# 1_STM32F334R8T6Board_MCU.net
KiCad netlist of a schematic drawn in Altium Designer
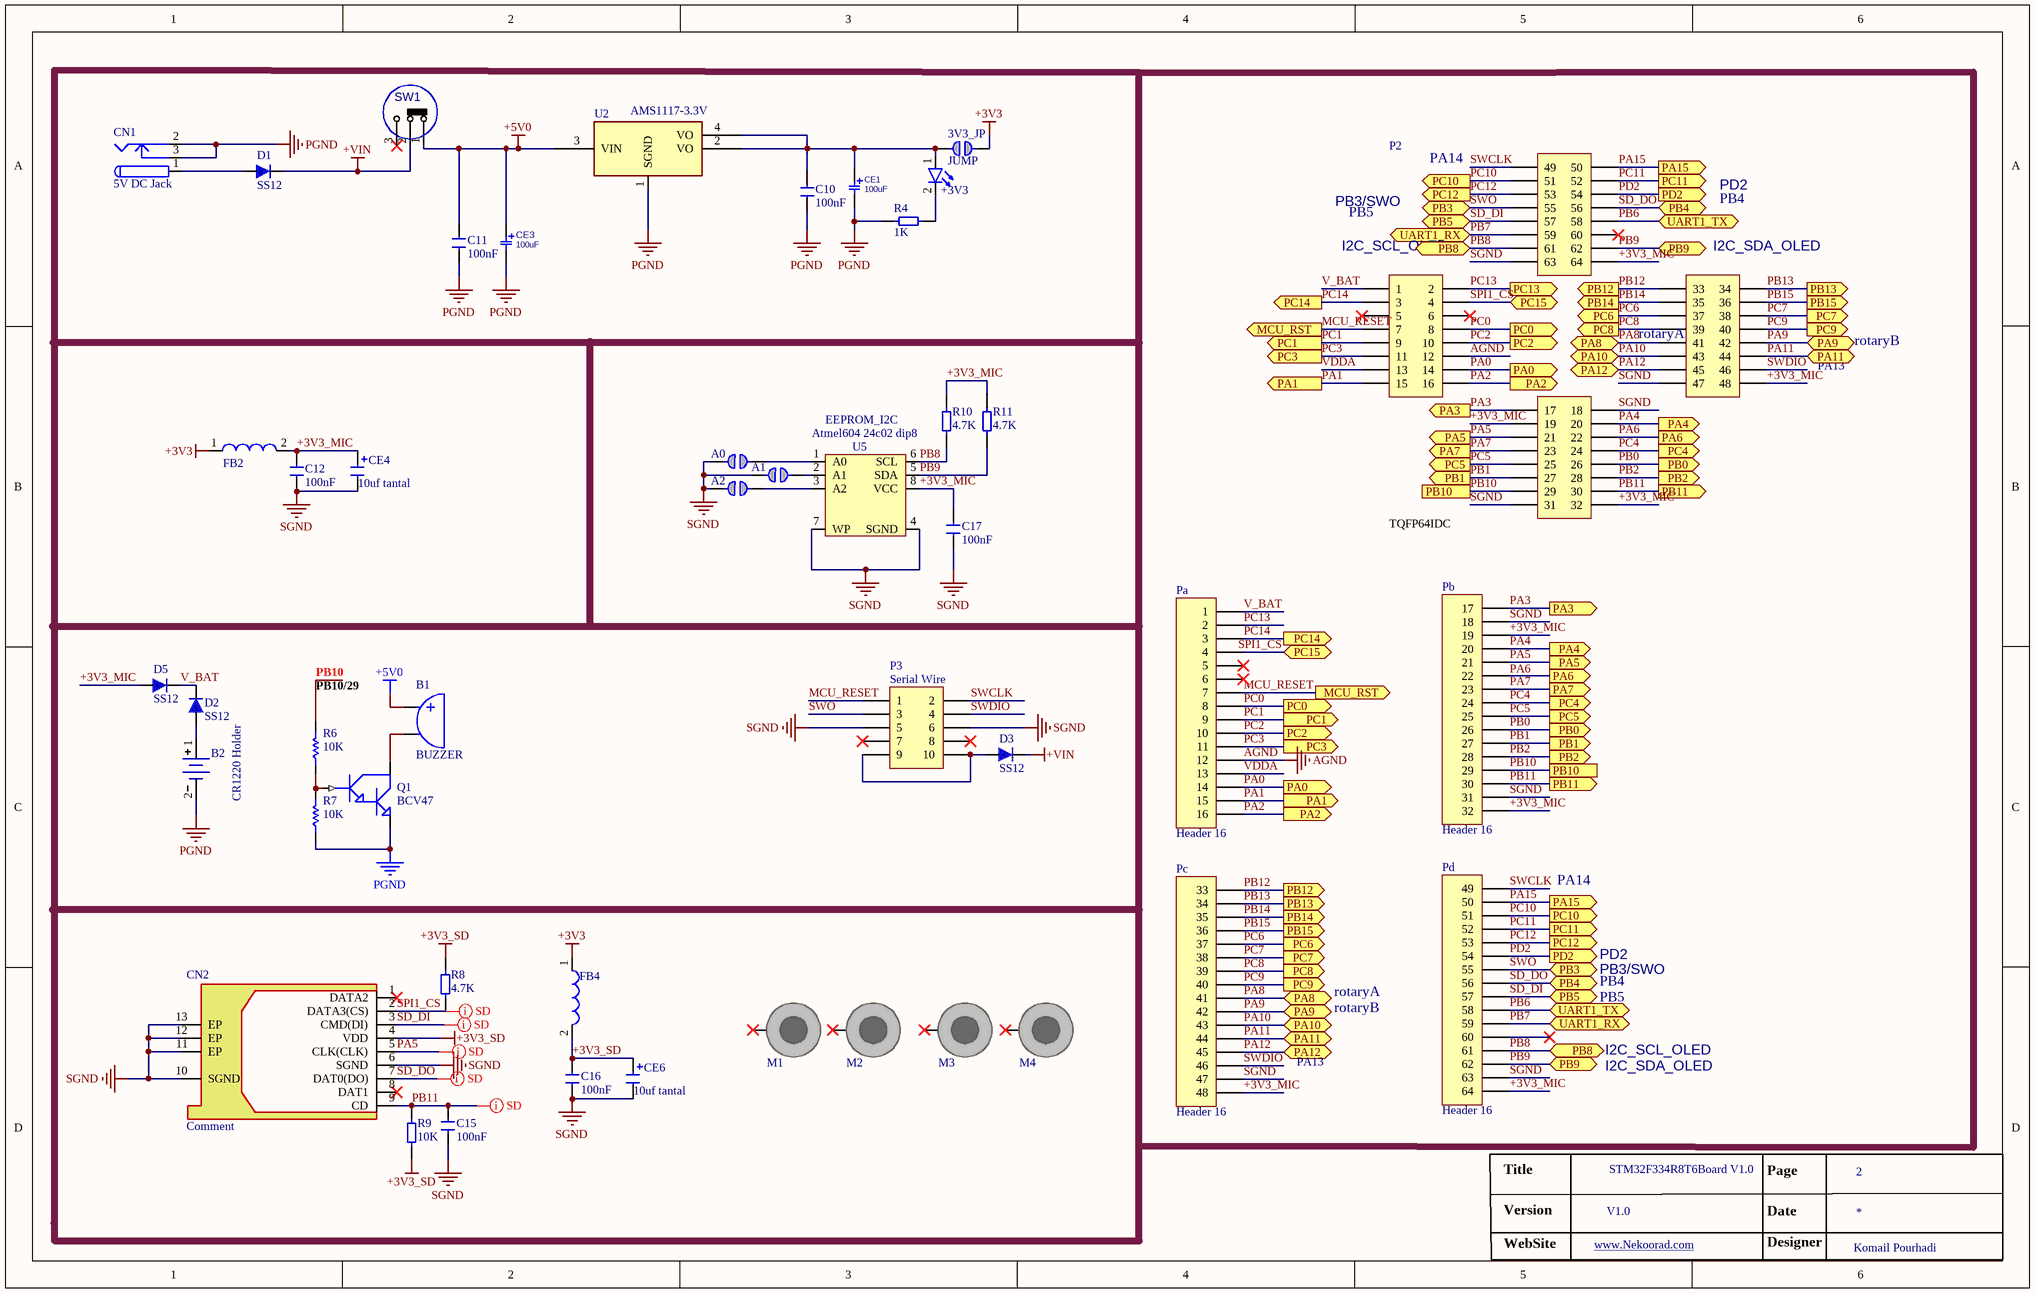
[diagram p0: [1]STM32F334R8T6Board_MCU.SchDoc]

(export (version "E")
  (design (tool "Eeschema 10.0.6"))
  (components
    (comp (ref "+3V3")
      (value "HB")
      (footprint "LED SMD 1206")
      (description "LED")
      (fields (field (name "DESIGNER") "Saeid Jorablo"))
      (libsource (lib "3D") (part "LED"))
    )
    (comp (ref "3V3_JP")
      (value "JUMP")
      (footprint "RES_1206")
      (libsource (lib "DotexGroup_LIB") (part "jumper SMD"))
    )
    (comp (ref "A0")
      (value "Comment")
      (footprint "HDR1X2")
      (libsource (lib "DotexGroup_LIB") (part "jumper SMD"))
    )
    (comp (ref "A1")
      (value "Comment")
      (footprint "HDR1X2")
      (libsource (lib "DotexGroup_LIB") (part "jumper SMD"))
    )
    (comp (ref "A2")
      (value "Comment")
      (footprint "HDR1X2")
      (libsource (lib "DotexGroup_LIB") (part "jumper SMD"))
    )
    (comp (ref "B1")
      (value "BUZZER")
      (footprint "BUZZ")
      (libsource (lib "Previous Backup of Device") (part "BUZZER"))
    )
    (comp (ref "B2")
      (value "CR1220 Holder")
      (footprint "Battery3")
      (libsource (lib "DotexGroup_LIB") (part "Battry Backup"))
    )
    (comp (ref "C10")
      (value "Comment")
      (footprint "SMD_CAP_1206")
      (fields (field (name "ALTIUM_UNNAMED_1") "100nF"))
      (libsource (lib "DotexGroup_LIB") (part "Capacitor SMD"))
    )
    (comp (ref "C11")
      (value "Comment")
      (footprint "SMD_CAP_1206")
      (fields (field (name "ALTIUM_UNNAMED_1") "100nF"))
      (libsource (lib "DotexGroup_LIB") (part "Capacitor SMD"))
    )
    (comp (ref "C12")
      (value "Comment")
      (footprint "SMD_CAP_1206")
      (fields (field (name "ALTIUM_UNNAMED_1") "100nF"))
      (libsource (lib "DotexGroup_LIB") (part "Capacitor SMD"))
    )
    (comp (ref "C15")
      (value "Comment")
      (footprint "SMD_CAP_1206")
      (fields (field (name "ALTIUM_UNNAMED_1") "100nF"))
      (libsource (lib "DotexGroup_LIB") (part "Capacitor SMD"))
    )
    (comp (ref "C16")
      (value "Comment")
      (footprint "SMD_CAP_1206")
      (fields (field (name "ALTIUM_UNNAMED_1") "100nF"))
      (libsource (lib "DotexGroup_LIB") (part "Capacitor SMD"))
    )
    (comp (ref "C17")
      (value "Comment")
      (footprint "SMD_CAP_1206")
      (fields (field (name "ALTIUM_UNNAMED_1") "100nF"))
      (libsource (lib "DotexGroup_LIB") (part "Capacitor SMD"))
    )
    (comp (ref "CE1")
      (value "100uF")
      (footprint "CAP-E-4")
      (description "CAP, THD, ELEC, 10uF, 25V")
      (fields (field (name "MANF") "MANF") (field (name "MANF_P#") "MANF_PART#"))
      (libsource (lib "DotexGroup_LIB") (part "CAP_THD_EL_10u25V"))
    )
    (comp (ref "CE3")
      (value "100uF")
      (footprint "CAP-E-4")
      (description "CAP, THD, ELEC, 10uF, 25V")
      (fields (field (name "MANF") "MANF") (field (name "MANF_P#") "MANF_PART#"))
      (libsource (lib "DotexGroup_LIB") (part "CAP_THD_EL_10u25V"))
    )
    (comp (ref "CE4")
      (value "10uf tantal")
      (footprint "cap-e-2")
      (libsource (lib "DotexGroup_LIB") (part "Capacitor Tantalium"))
    )
    (comp (ref "CE6")
      (value "10uf tantal")
      (footprint "cap-e-2")
      (libsource (lib "DotexGroup_LIB") (part "Capacitor Tantalium"))
    )
    (comp (ref "CN1")
      (value "5V DC Jack")
      (footprint "Power Jack")
      (libsource (lib "DotexGroup_LIB") (part "Power Jack"))
    )
    (comp (ref "CN2")
      (value "Comment")
      (footprint "Micro sd csrd")
      (libsource (lib "DotexGroup_LIB") (part "Micro SD Card"))
    )
    (comp (ref "D1")
      (value "SS12")
      (footprint "Diode SMA-M")
      (libsource (lib "DotexGroup_LIB") (part "1N4001"))
    )
    (comp (ref "D2")
      (value "SS12")
      (footprint "Diode SMA-M")
      (libsource (lib "DotexGroup_LIB") (part "1N4001"))
    )
    (comp (ref "D3")
      (value "SS12")
      (footprint "Diode SMA-M")
      (libsource (lib "DotexGroup_LIB") (part "1N4001"))
    )
    (comp (ref "D5")
      (value "SS12")
      (footprint "Diode SMA-M")
      (libsource (lib "DotexGroup_LIB") (part "1N4001"))
    )
    (comp (ref "FB2")
      (value "Comment")
      (footprint "r4p")
      (libsource (lib "DotexGroup_LIB") (part "Ferrit Bead"))
    )
    (comp (ref "FB4")
      (value "Comment")
      (footprint "r4p")
      (libsource (lib "DotexGroup_LIB") (part "Ferrit Bead"))
    )
    (comp (ref "M1")
      (value "Comment")
      (footprint "Stud-hole")
      (description "SCREW mouting, M1.6, 1.6mm diameter and 3.2mm PanHead")
      (libsource (lib "DotexGroup_LIB") (part "SCMH_M1P6"))
    )
    (comp (ref "M2")
      (value "Comment")
      (footprint "Stud-hole")
      (description "SCREW mouting, M1.6, 1.6mm diameter and 3.2mm PanHead")
      (libsource (lib "DotexGroup_LIB") (part "SCMH_M1P6"))
    )
    (comp (ref "M3")
      (value "Comment")
      (footprint "Stud-hole")
      (description "SCREW mouting, M1.6, 1.6mm diameter and 3.2mm PanHead")
      (libsource (lib "DotexGroup_LIB") (part "SCMH_M1P6"))
    )
    (comp (ref "M4")
      (value "Comment")
      (footprint "Stud-hole")
      (description "SCREW mouting, M1.6, 1.6mm diameter and 3.2mm PanHead")
      (libsource (lib "DotexGroup_LIB") (part "SCMH_M1P6"))
    )
    (comp (ref "P2")
      (value "TQFP64IDC")
      (footprint "tqfp64idc")
      (libsource (lib "Mylibrary2019") (part "TQFP64IDC"))
    )
    (comp (ref "P3")
      (value "Serial Wire")
      (footprint "IDC10-BOX")
      (description "Header, 5-Pin, Dual row")
      (fields (field (name "PUBLISHER") "Altium Limited"))
      (libsource (lib "Miscellaneous Connectors") (part "Header 5X2"))
    )
    (comp (ref "Pa")
      (value "Header 16")
      (footprint "HDR1X16")
      (description "Header, 16-Pin")
      (fields (field (name "PUBLISHER") "Altium Limited"))
      (libsource (lib "") (part "Header 16_1"))
    )
    (comp (ref "Pb")
      (value "Header 16")
      (footprint "HDR1X16")
      (description "Header, 16-Pin")
      (fields (field (name "PUBLISHER") "Altium Limited"))
      (libsource (lib "") (part "Header 16_3"))
    )
    (comp (ref "Pc")
      (value "Header 16")
      (footprint "HDR1X16")
      (description "Header, 16-Pin")
      (fields (field (name "PUBLISHER") "Altium Limited"))
      (libsource (lib "") (part "Header 16_2"))
    )
    (comp (ref "Pd")
      (value "Header 16")
      (footprint "HDR1X16")
      (description "Header, 16-Pin")
      (fields (field (name "PUBLISHER") "Altium Limited"))
      (libsource (lib "Miscellaneous Connectors") (part "Header 16"))
    )
    (comp (ref "Q1")
      (value "BCV47")
      (footprint "SOT23_BEC_M")
      (libsource (lib "MyAltiumLib") (part "NPN DAR"))
    )
    (comp (ref "R4")
      (value "Comment")
      (footprint "RES_1206")
      (fields (field (name "ALTIUM_UNNAMED_1") "1K"))
      (libsource (lib "DotexGroup_LIB") (part "Resistor SMD"))
    )
    (comp (ref "R6")
      (value "10K")
      (footprint "RES_1206")
      (description "Resistor")
      (fields (field (name "TOLERANCE") "5%") (field (name "POWER") "1/8 W"))
      (libsource (lib "My Library") (part "Resistor"))
    )
    (comp (ref "R7")
      (value "10K")
      (footprint "RES_1206")
      (description "Resistor")
      (fields (field (name "TOLERANCE") "5%") (field (name "POWER") "1/8 W"))
      (libsource (lib "My Library") (part "Resistor"))
    )
    (comp (ref "R8")
      (value "Comment")
      (footprint "RES_1206")
      (fields (field (name "ALTIUM_UNNAMED_1") "4.7K"))
      (libsource (lib "DotexGroup_LIB") (part "Resistor SMD"))
    )
    (comp (ref "R9")
      (value "Comment")
      (footprint "RES_1206")
      (fields (field (name "ALTIUM_UNNAMED_1") "10K"))
      (libsource (lib "DotexGroup_LIB") (part "Resistor SMD"))
    )
    (comp (ref "R10")
      (value "Comment")
      (footprint "RES_1206")
      (fields (field (name "ALTIUM_UNNAMED_1") "4.7K"))
      (libsource (lib "DotexGroup_LIB") (part "Resistor SMD"))
    )
    (comp (ref "R11")
      (value "Comment")
      (footprint "RES_1206")
      (fields (field (name "ALTIUM_UNNAMED_1") "4.7K"))
      (libsource (lib "DotexGroup_LIB") (part "Resistor SMD"))
    )
    (comp (ref "SW1")
      (value "SlideSwitch")
      (footprint "HDR1X3")
      (description "SWITCH, SLIDE, SPDT, 8.6X4.3mm, THD")
      (fields (field (name "MANF") "C&K") (field (name "MANF_PART#") "OS102011MS2QN1"))
      (libsource (lib "DotexGroup_LIB") (part "SWSLIDT_SPDT_S_8X4"))
    )
    (comp (ref "U2")
      (value "AMS1117-3.3V")
      (footprint "MP04A_M")
      (description "REG, Linear, LDO1V, 0.8A, SOT-223")
      (fields
        (field (name "MANF_P#") "LD1117, LM1117, AMS1117, TLV1117, REG1117, NCP1117, LT1117, SPX1117")
        (field (name "MANF") "TI, ON, ST")
      )
      (libsource (lib "DotexGroup_LIB") (part "VREG_1117_SOT223"))
    )
    (comp (ref "U5")
      (value "EEPROM_I2C")
      (footprint "dip8")
      (libsource (lib "DotexGroup_LIB") (part "AT24C128"))
    )
  )
  (nets
    (net (code "1") (name "+3V3") (class "Default")
      (node (ref "3V3_JP") (pin "2") (pintype "passive"))
      (node (ref "FB2") (pin "1") (pinfunction "1_1") (pintype "passive"))
      (node (ref "FB4") (pin "1") (pinfunction "1_1") (pintype "passive"))
    )
    (net (code "2") (name "+3V3_SD") (class "Default")
      (node (ref "C16") (pin "2") (pintype "passive"))
      (node (ref "CE6") (pin "1") (pintype "passive"))
      (node (ref "CN2") (pin "4") (pinfunction "VDD_4") (pintype "passive"))
      (node (ref "FB4") (pin "2") (pinfunction "2_2") (pintype "passive"))
      (node (ref "R8") (pin "1") (pintype "passive"))
      (node (ref "R9") (pin "2") (pintype "passive"))
    )
    (net (code "3") (name "+5V0") (class "Default")
      (node (ref "B1") (pin "1") (pintype "passive"))
      (node (ref "C11") (pin "2") (pintype "passive"))
      (node (ref "CE3") (pin "1") (pinfunction "1_1") (pintype "passive"))
      (node (ref "SW1") (pin "1") (pinfunction "P1_1") (pintype "passive"))
      (node (ref "U2") (pin "3") (pinfunction "VIN_3") (pintype "passive"))
    )
    (net (code "4") (name "+VIN") (class "Default")
      (node (ref "D1") (pin "2") (pinfunction "K_2") (pintype "passive"))
      (node (ref "D3") (pin "2") (pinfunction "K_2") (pintype "passive"))
      (node (ref "SW1") (pin "2") (pinfunction "P3_2") (pintype "passive"))
    )
    (net (code "5") (name "/+3V3_MIC") (class "Default")
      (node (ref "C12") (pin "2") (pintype "passive"))
      (node (ref "C17") (pin "2") (pintype "passive"))
      (node (ref "CE4") (pin "1") (pintype "passive"))
      (node (ref "D5") (pin "1") (pinfunction "A_1") (pintype "passive"))
      (node (ref "FB2") (pin "2") (pinfunction "2_2") (pintype "passive"))
      (node (ref "P2") (pin "19") (pinfunction "19_19") (pintype "passive"))
      (node (ref "P2") (pin "32") (pinfunction "32_32") (pintype "passive"))
      (node (ref "P2") (pin "48") (pinfunction "48_48") (pintype "passive"))
      (node (ref "P2") (pin "64") (pinfunction "64_64") (pintype "passive"))
      (node (ref "Pb") (pin "19") (pinfunction "19_19") (pintype "passive"))
      (node (ref "Pb") (pin "32") (pinfunction "32_32") (pintype "passive"))
      (node (ref "Pc") (pin "48") (pinfunction "48_48") (pintype "passive"))
      (node (ref "Pd") (pin "64") (pinfunction "64_64") (pintype "passive"))
      (node (ref "R10") (pin "1") (pintype "passive"))
      (node (ref "R11") (pin "1") (pintype "passive"))
      (node (ref "U5") (pin "8") (pinfunction "VCC_8") (pintype "passive"))
    )
    (net (code "6") (name "/MCU_RESET") (class "Default")
      (node (ref "P2") (pin "7") (pinfunction "7_7") (pintype "passive"))
      (node (ref "P3") (pin "1") (pinfunction "1_1") (pintype "passive"))
      (node (ref "Pa") (pin "7") (pinfunction "7_7") (pintype "passive"))
    )
    (net (code "7") (name "/PA0") (class "Default")
      (node (ref "P2") (pin "14") (pinfunction "14_14") (pintype "passive"))
      (node (ref "Pa") (pin "14") (pinfunction "14_14") (pintype "passive"))
    )
    (net (code "8") (name "/PA1") (class "Default")
      (node (ref "P2") (pin "15") (pinfunction "15_15") (pintype "passive"))
      (node (ref "Pa") (pin "15") (pinfunction "15_15") (pintype "passive"))
    )
    (net (code "9") (name "/PA2") (class "Default")
      (node (ref "P2") (pin "16") (pinfunction "16_16") (pintype "passive"))
      (node (ref "Pa") (pin "16") (pinfunction "16_16") (pintype "passive"))
    )
    (net (code "10") (name "/PA3") (class "Default")
      (node (ref "P2") (pin "17") (pinfunction "17_17") (pintype "passive"))
      (node (ref "Pb") (pin "17") (pinfunction "17_17") (pintype "passive"))
    )
    (net (code "11") (name "/PA4") (class "Default")
      (node (ref "P2") (pin "20") (pinfunction "20_20") (pintype "passive"))
      (node (ref "Pb") (pin "20") (pinfunction "20_20") (pintype "passive"))
    )
    (net (code "12") (name "/PA5") (class "Default")
      (node (ref "CN2") (pin "5") (pinfunction "CLK(CLK)_5") (pintype "passive"))
      (node (ref "P2") (pin "21") (pinfunction "21_21") (pintype "passive"))
      (node (ref "Pb") (pin "21") (pinfunction "21_21") (pintype "passive"))
    )
    (net (code "13") (name "/PA6") (class "Default")
      (node (ref "P2") (pin "22") (pinfunction "22_22") (pintype "passive"))
      (node (ref "Pb") (pin "22") (pinfunction "22_22") (pintype "passive"))
    )
    (net (code "14") (name "/PA7") (class "Default")
      (node (ref "P2") (pin "23") (pinfunction "23_23") (pintype "passive"))
      (node (ref "Pb") (pin "23") (pinfunction "23_23") (pintype "passive"))
    )
    (net (code "15") (name "/PA8") (class "Default")
      (node (ref "P2") (pin "41") (pinfunction "41_41") (pintype "passive"))
      (node (ref "Pc") (pin "41") (pinfunction "41_41") (pintype "passive"))
    )
    (net (code "16") (name "/PA9") (class "Default")
      (node (ref "P2") (pin "42") (pinfunction "42_42") (pintype "passive"))
      (node (ref "Pc") (pin "42") (pinfunction "42_42") (pintype "passive"))
    )
    (net (code "17") (name "/PA10") (class "Default")
      (node (ref "P2") (pin "43") (pinfunction "43_43") (pintype "passive"))
      (node (ref "Pc") (pin "43") (pinfunction "43_43") (pintype "passive"))
    )
    (net (code "18") (name "/PA11") (class "Default")
      (node (ref "P2") (pin "44") (pinfunction "44_44") (pintype "passive"))
      (node (ref "Pc") (pin "44") (pinfunction "44_44") (pintype "passive"))
    )
    (net (code "19") (name "/PA12") (class "Default")
      (node (ref "P2") (pin "45") (pinfunction "45_45") (pintype "passive"))
      (node (ref "Pc") (pin "45") (pinfunction "45_45") (pintype "passive"))
    )
    (net (code "20") (name "/PA15") (class "Default")
      (node (ref "P2") (pin "50") (pinfunction "50_50") (pintype "passive"))
      (node (ref "Pd") (pin "50") (pinfunction "50_50") (pintype "passive"))
    )
    (net (code "21") (name "/PB0") (class "Default")
      (node (ref "P2") (pin "26") (pinfunction "26_26") (pintype "passive"))
      (node (ref "Pb") (pin "26") (pinfunction "26_26") (pintype "passive"))
    )
    (net (code "22") (name "/PB1") (class "Default")
      (node (ref "P2") (pin "27") (pinfunction "27_27") (pintype "passive"))
      (node (ref "Pb") (pin "27") (pinfunction "27_27") (pintype "passive"))
    )
    (net (code "23") (name "/PB2") (class "Default")
      (node (ref "P2") (pin "28") (pinfunction "28_28") (pintype "passive"))
      (node (ref "Pb") (pin "28") (pinfunction "28_28") (pintype "passive"))
    )
    (net (code "24") (name "/PB6") (class "Default")
      (node (ref "P2") (pin "58") (pinfunction "58_58") (pintype "passive"))
      (node (ref "Pd") (pin "58") (pinfunction "58_58") (pintype "passive"))
    )
    (net (code "25") (name "/PB7") (class "Default")
      (node (ref "P2") (pin "59") (pinfunction "59_59") (pintype "passive"))
      (node (ref "Pd") (pin "59") (pinfunction "59_59") (pintype "passive"))
    )
    (net (code "26") (name "/PB8") (class "Default")
      (node (ref "P2") (pin "61") (pinfunction "61_61") (pintype "passive"))
      (node (ref "Pd") (pin "61") (pinfunction "61_61") (pintype "passive"))
      (node (ref "R10") (pin "2") (pintype "passive"))
      (node (ref "U5") (pin "6") (pinfunction "SCL_6") (pintype "passive"))
    )
    (net (code "27") (name "/PB9") (class "Default")
      (node (ref "P2") (pin "62") (pinfunction "62_62") (pintype "passive"))
      (node (ref "Pd") (pin "62") (pinfunction "62_62") (pintype "passive"))
      (node (ref "R11") (pin "2") (pintype "passive"))
      (node (ref "U5") (pin "5") (pinfunction "SDA_5") (pintype "passive"))
    )
    (net (code "28") (name "/PB10") (class "Default")
      (node (ref "P2") (pin "29") (pinfunction "29_29") (pintype "passive"))
      (node (ref "Pb") (pin "29") (pinfunction "29_29") (pintype "passive"))
      (node (ref "R6") (pin "2") (pinfunction "2_2") (pintype "passive"))
    )
    (net (code "29") (name "/PB11") (class "Default")
      (node (ref "C15") (pin "1") (pintype "passive"))
      (node (ref "CN2") (pin "9") (pinfunction "CD_9") (pintype "passive"))
      (node (ref "P2") (pin "30") (pinfunction "30_30") (pintype "passive"))
      (node (ref "Pb") (pin "30") (pinfunction "30_30") (pintype "passive"))
      (node (ref "R9") (pin "1") (pintype "passive"))
    )
    (net (code "30") (name "/PB12") (class "Default")
      (node (ref "P2") (pin "33") (pinfunction "33_33") (pintype "passive"))
      (node (ref "Pc") (pin "33") (pinfunction "33_33") (pintype "passive"))
    )
    (net (code "31") (name "/PB13") (class "Default")
      (node (ref "P2") (pin "34") (pinfunction "34_34") (pintype "passive"))
      (node (ref "Pc") (pin "34") (pinfunction "34_34") (pintype "passive"))
    )
    (net (code "32") (name "/PB14") (class "Default")
      (node (ref "P2") (pin "35") (pinfunction "35_35") (pintype "passive"))
      (node (ref "Pc") (pin "35") (pinfunction "35_35") (pintype "passive"))
    )
    (net (code "33") (name "/PB15") (class "Default")
      (node (ref "P2") (pin "36") (pinfunction "36_36") (pintype "passive"))
      (node (ref "Pc") (pin "36") (pinfunction "36_36") (pintype "passive"))
    )
    (net (code "34") (name "/PC0") (class "Default")
      (node (ref "P2") (pin "8") (pinfunction "8_8") (pintype "passive"))
      (node (ref "Pa") (pin "8") (pinfunction "8_8") (pintype "passive"))
    )
    (net (code "35") (name "/PC1") (class "Default")
      (node (ref "P2") (pin "9") (pinfunction "9_9") (pintype "passive"))
      (node (ref "Pa") (pin "9") (pinfunction "9_9") (pintype "passive"))
    )
    (net (code "36") (name "/PC2") (class "Default")
      (node (ref "P2") (pin "10") (pinfunction "10_10") (pintype "passive"))
      (node (ref "Pa") (pin "10") (pinfunction "10_10") (pintype "passive"))
    )
    (net (code "37") (name "/PC3") (class "Default")
      (node (ref "P2") (pin "11") (pinfunction "11_11") (pintype "passive"))
      (node (ref "Pa") (pin "11") (pinfunction "11_11") (pintype "passive"))
    )
    (net (code "38") (name "/PC4") (class "Default")
      (node (ref "P2") (pin "24") (pinfunction "24_24") (pintype "passive"))
      (node (ref "Pb") (pin "24") (pinfunction "24_24") (pintype "passive"))
    )
    (net (code "39") (name "/PC5") (class "Default")
      (node (ref "P2") (pin "25") (pinfunction "25_25") (pintype "passive"))
      (node (ref "Pb") (pin "25") (pinfunction "25_25") (pintype "passive"))
    )
    (net (code "40") (name "/PC6") (class "Default")
      (node (ref "P2") (pin "37") (pinfunction "37_37") (pintype "passive"))
      (node (ref "Pc") (pin "37") (pinfunction "37_37") (pintype "passive"))
    )
    (net (code "41") (name "/PC7") (class "Default")
      (node (ref "P2") (pin "38") (pinfunction "38_38") (pintype "passive"))
      (node (ref "Pc") (pin "38") (pinfunction "38_38") (pintype "passive"))
    )
    (net (code "42") (name "/PC8") (class "Default")
      (node (ref "P2") (pin "39") (pinfunction "39_39") (pintype "passive"))
      (node (ref "Pc") (pin "39") (pinfunction "39_39") (pintype "passive"))
    )
    (net (code "43") (name "/PC9") (class "Default")
      (node (ref "P2") (pin "40") (pinfunction "40_40") (pintype "passive"))
      (node (ref "Pc") (pin "40") (pinfunction "40_40") (pintype "passive"))
    )
    (net (code "44") (name "/PC10") (class "Default")
      (node (ref "P2") (pin "51") (pinfunction "51_51") (pintype "passive"))
      (node (ref "Pd") (pin "51") (pinfunction "51_51") (pintype "passive"))
    )
    (net (code "45") (name "/PC11") (class "Default")
      (node (ref "P2") (pin "52") (pinfunction "52_52") (pintype "passive"))
      (node (ref "Pd") (pin "52") (pinfunction "52_52") (pintype "passive"))
    )
    (net (code "46") (name "/PC12") (class "Default")
      (node (ref "P2") (pin "53") (pinfunction "53_53") (pintype "passive"))
      (node (ref "Pd") (pin "53") (pinfunction "53_53") (pintype "passive"))
    )
    (net (code "47") (name "/PC13") (class "Default")
      (node (ref "P2") (pin "2") (pinfunction "2_2") (pintype "passive"))
      (node (ref "Pa") (pin "2") (pinfunction "2_2") (pintype "passive"))
    )
    (net (code "48") (name "/PC14") (class "Default")
      (node (ref "P2") (pin "3") (pinfunction "3_3") (pintype "passive"))
      (node (ref "Pa") (pin "3") (pinfunction "3_3") (pintype "passive"))
    )
    (net (code "49") (name "/PD2") (class "Default")
      (node (ref "P2") (pin "54") (pinfunction "54_54") (pintype "passive"))
      (node (ref "Pd") (pin "54") (pinfunction "54_54") (pintype "passive"))
    )
    (net (code "50") (name "/SD_DI") (class "Default")
      (node (ref "CN2") (pin "3") (pinfunction "CMD(DI)_3") (pintype "passive"))
      (node (ref "P2") (pin "57") (pinfunction "57_57") (pintype "passive"))
      (node (ref "Pd") (pin "57") (pinfunction "57_57") (pintype "passive"))
    )
    (net (code "51") (name "/SD_DO") (class "Default")
      (node (ref "CN2") (pin "7") (pinfunction "DAT0(DO)_7") (pintype "passive"))
      (node (ref "P2") (pin "56") (pinfunction "56_56") (pintype "passive"))
      (node (ref "Pd") (pin "56") (pinfunction "56_56") (pintype "passive"))
    )
    (net (code "52") (name "/SPI1_CS") (class "Default")
      (node (ref "CN2") (pin "2") (pinfunction "DATA3(CS)_2") (pintype "passive"))
      (node (ref "P2") (pin "4") (pinfunction "4_4") (pintype "passive"))
      (node (ref "Pa") (pin "4") (pinfunction "4_4") (pintype "passive"))
      (node (ref "R8") (pin "2") (pintype "passive"))
    )
    (net (code "53") (name "/SWCLK") (class "Default")
      (node (ref "P2") (pin "49") (pinfunction "49_49") (pintype "passive"))
      (node (ref "P3") (pin "2") (pinfunction "2_2") (pintype "passive"))
      (node (ref "Pd") (pin "49") (pinfunction "49_49") (pintype "passive"))
    )
    (net (code "54") (name "/SWDIO") (class "Default")
      (node (ref "P2") (pin "46") (pinfunction "46_46") (pintype "passive"))
      (node (ref "P3") (pin "4") (pinfunction "4_4") (pintype "passive"))
      (node (ref "Pc") (pin "46") (pinfunction "46_46") (pintype "passive"))
    )
    (net (code "55") (name "/SWO") (class "Default")
      (node (ref "P2") (pin "55") (pinfunction "55_55") (pintype "passive"))
      (node (ref "P3") (pin "3") (pinfunction "3_3") (pintype "passive"))
      (node (ref "Pd") (pin "55") (pinfunction "55_55") (pintype "passive"))
    )
    (net (code "56") (name "/VDDA") (class "Default")
      (node (ref "P2") (pin "13") (pinfunction "13_13") (pintype "passive"))
      (node (ref "Pa") (pin "13") (pinfunction "13_13") (pintype "passive"))
    )
    (net (code "57") (name "/V_BAT") (class "Default")
      (node (ref "D2") (pin "2") (pinfunction "K_2") (pintype "passive"))
      (node (ref "D5") (pin "2") (pinfunction "K_2") (pintype "passive"))
      (node (ref "P2") (pin "1") (pinfunction "1_1") (pintype "passive"))
      (node (ref "Pa") (pin "1") (pinfunction "1_1") (pintype "passive"))
    )
    (net (code "58") (name "AGND") (class "Default")
      (node (ref "P2") (pin "12") (pinfunction "12_12") (pintype "passive"))
      (node (ref "Pa") (pin "12") (pinfunction "12_12") (pintype "passive"))
    )
    (net (code "59") (name "Net-(+3V3-A)") (class "Default")
      (node (ref "+3V3") (pin "1") (pinfunction "A_1") (pintype "passive"))
      (node (ref "3V3_JP") (pin "1") (pintype "passive"))
      (node (ref "C10") (pin "2") (pintype "passive"))
      (node (ref "CE1") (pin "1") (pinfunction "1_1") (pintype "passive"))
      (node (ref "U2") (pin "2") (pinfunction "VO_2") (pintype "passive"))
      (node (ref "U2") (pin "4") (pinfunction "VO_4") (pintype "passive"))
    )
    (net (code "60") (name "Net-(+3V3-K)") (class "Default")
      (node (ref "+3V3") (pin "2") (pinfunction "K_2") (pintype "passive"))
      (node (ref "R4") (pin "1") (pintype "passive"))
    )
    (net (code "61") (name "Net-(B2-+)") (class "Default")
      (node (ref "B2") (pin "1") (pinfunction "+_1") (pintype "passive"))
      (node (ref "D2") (pin "1") (pinfunction "A_1") (pintype "passive"))
    )
    (net (code "62") (name "Net-(D1-A)") (class "Default")
      (node (ref "CN1") (pin "1") (pinfunction "1_1") (pintype "power_in"))
      (node (ref "D1") (pin "1") (pinfunction "A_1") (pintype "passive"))
    )
    (net (code "63") (name "Net-(D3-A)") (class "Default")
      (node (ref "D3") (pin "1") (pinfunction "A_1") (pintype "passive"))
      (node (ref "P3") (pin "10") (pinfunction "10_10") (pintype "passive"))
      (node (ref "P3") (pin "9") (pinfunction "9_9") (pintype "passive"))
    )
    (net (code "64") (name "Net-(Q1-B)") (class "Default")
      (node (ref "Q1") (pin "1") (pinfunction "B_1") (pintype "input"))
      (node (ref "R6") (pin "1") (pinfunction "1_1") (pintype "passive"))
      (node (ref "R7") (pin "2") (pinfunction "2_2") (pintype "passive"))
    )
    (net (code "65") (name "Net-(Q1-C)") (class "Default")
      (node (ref "B1") (pin "2") (pintype "passive"))
      (node (ref "Q1") (pin "3") (pinfunction "C_3") (pintype "passive"))
    )
    (net (code "66") (name "Net-(U5-A0)") (class "Default")
      (node (ref "A0") (pin "2") (pintype "passive"))
      (node (ref "U5") (pin "1") (pinfunction "A0_1") (pintype "passive"))
    )
    (net (code "67") (name "Net-(U5-A1)") (class "Default")
      (node (ref "A1") (pin "2") (pintype "passive"))
      (node (ref "U5") (pin "2") (pinfunction "A1_2") (pintype "passive"))
    )
    (net (code "68") (name "Net-(U5-A2)") (class "Default")
      (node (ref "A2") (pin "2") (pintype "passive"))
      (node (ref "U5") (pin "3") (pinfunction "A2_3") (pintype "passive"))
    )
    (net (code "69") (name "PGND") (class "Default")
      (node (ref "B2") (pin "2") (pinfunction "-_2") (pintype "passive"))
      (node (ref "C10") (pin "1") (pintype "passive"))
      (node (ref "C11") (pin "1") (pintype "passive"))
      (node (ref "CE1") (pin "2") (pinfunction "2_2") (pintype "passive"))
      (node (ref "CE3") (pin "2") (pinfunction "2_2") (pintype "passive"))
      (node (ref "CN1") (pin "2") (pinfunction "2_2") (pintype "power_in"))
      (node (ref "CN1") (pin "3") (pinfunction "3_3") (pintype "power_in"))
      (node (ref "Q1") (pin "2") (pinfunction "E_2") (pintype "passive"))
      (node (ref "R4") (pin "2") (pintype "passive"))
      (node (ref "R7") (pin "1") (pinfunction "1_1") (pintype "passive"))
      (node (ref "U2") (pin "1") (pinfunction "SGND_1") (pintype "passive"))
    )
    (net (code "70") (name "SGND") (class "Default")
      (node (ref "A0") (pin "1") (pintype "passive"))
      (node (ref "A1") (pin "1") (pintype "passive"))
      (node (ref "A2") (pin "1") (pintype "passive"))
      (node (ref "C12") (pin "1") (pintype "passive"))
      (node (ref "C15") (pin "2") (pintype "passive"))
      (node (ref "C16") (pin "1") (pintype "passive"))
      (node (ref "C17") (pin "1") (pintype "passive"))
      (node (ref "CE4") (pin "2") (pintype "passive"))
      (node (ref "CE6") (pin "2") (pintype "passive"))
      (node (ref "CN2") (pin "10") (pinfunction "SGND_10") (pintype "passive"))
      (node (ref "CN2") (pin "11") (pinfunction "EP_11") (pintype "passive"))
      (node (ref "CN2") (pin "12") (pinfunction "EP_12") (pintype "passive"))
      (node (ref "CN2") (pin "13") (pinfunction "EP_13") (pintype "passive"))
      (node (ref "CN2") (pin "6") (pinfunction "SGND_6") (pintype "passive"))
      (node (ref "P2") (pin "18") (pinfunction "18_18") (pintype "passive"))
      (node (ref "P2") (pin "31") (pinfunction "31_31") (pintype "passive"))
      (node (ref "P2") (pin "47") (pinfunction "47_47") (pintype "passive"))
      (node (ref "P2") (pin "63") (pinfunction "63_63") (pintype "passive"))
      (node (ref "P3") (pin "5") (pinfunction "5_5") (pintype "passive"))
      (node (ref "P3") (pin "6") (pinfunction "6_6") (pintype "passive"))
      (node (ref "Pb") (pin "18") (pinfunction "18_18") (pintype "passive"))
      (node (ref "Pb") (pin "31") (pinfunction "31_31") (pintype "passive"))
      (node (ref "Pc") (pin "47") (pinfunction "47_47") (pintype "passive"))
      (node (ref "Pd") (pin "63") (pinfunction "63_63") (pintype "passive"))
      (node (ref "U5") (pin "4") (pinfunction "SGND_4") (pintype "passive"))
      (node (ref "U5") (pin "7") (pinfunction "WP_7") (pintype "passive"))
    )
    (net (code "71") (name "unconnected-(CN2-DAT1-Pad8)") (class "Default")
      (node (ref "CN2") (pin "8") (pinfunction "DAT1_8") (pintype "passive+no_connect"))
    )
    (net (code "72") (name "unconnected-(CN2-DATA2-Pad1)") (class "Default")
      (node (ref "CN2") (pin "1") (pinfunction "DATA2_1") (pintype "passive+no_connect"))
    )
    (net (code "73") (name "unconnected-(M1-Pad1)") (class "Default")
      (node (ref "M1") (pin "1") (pinfunction "1_1") (pintype "passive+no_connect"))
    )
    (net (code "74") (name "unconnected-(M2-Pad1)") (class "Default")
      (node (ref "M2") (pin "1") (pinfunction "1_1") (pintype "passive+no_connect"))
    )
    (net (code "75") (name "unconnected-(M3-Pad1)") (class "Default")
      (node (ref "M3") (pin "1") (pinfunction "1_1") (pintype "passive+no_connect"))
    )
    (net (code "76") (name "unconnected-(M4-Pad1)") (class "Default")
      (node (ref "M4") (pin "1") (pinfunction "1_1") (pintype "passive+no_connect"))
    )
    (net (code "77") (name "unconnected-(P2-Pad5)") (class "Default")
      (node (ref "P2") (pin "5") (pinfunction "5_5") (pintype "passive+no_connect"))
    )
    (net (code "78") (name "unconnected-(P2-Pad6)") (class "Default")
      (node (ref "P2") (pin "6") (pinfunction "6_6") (pintype "passive+no_connect"))
    )
    (net (code "79") (name "unconnected-(P2-Pad60)") (class "Default")
      (node (ref "P2") (pin "60") (pinfunction "60_60") (pintype "passive+no_connect"))
    )
    (net (code "80") (name "unconnected-(P3-Pad7)") (class "Default")
      (node (ref "P3") (pin "7") (pinfunction "7_7") (pintype "passive+no_connect"))
    )
    (net (code "81") (name "unconnected-(P3-Pad8)") (class "Default")
      (node (ref "P3") (pin "8") (pinfunction "8_8") (pintype "passive+no_connect"))
    )
    (net (code "82") (name "unconnected-(Pa-Pad5)") (class "Default")
      (node (ref "Pa") (pin "5") (pinfunction "5_5") (pintype "passive+no_connect"))
    )
    (net (code "83") (name "unconnected-(Pa-Pad6)") (class "Default")
      (node (ref "Pa") (pin "6") (pinfunction "6_6") (pintype "passive+no_connect"))
    )
    (net (code "84") (name "unconnected-(Pd-Pad60)") (class "Default")
      (node (ref "Pd") (pin "60") (pinfunction "60_60") (pintype "passive+no_connect"))
    )
    (net (code "85") (name "unconnected-(SW1-P4-Pad3)") (class "Default")
      (node (ref "SW1") (pin "3") (pinfunction "P4_3") (pintype "passive+no_connect"))
    )
  )
)
